# testBoard.net
KiCad netlist of a schematic drawn in EAGLE
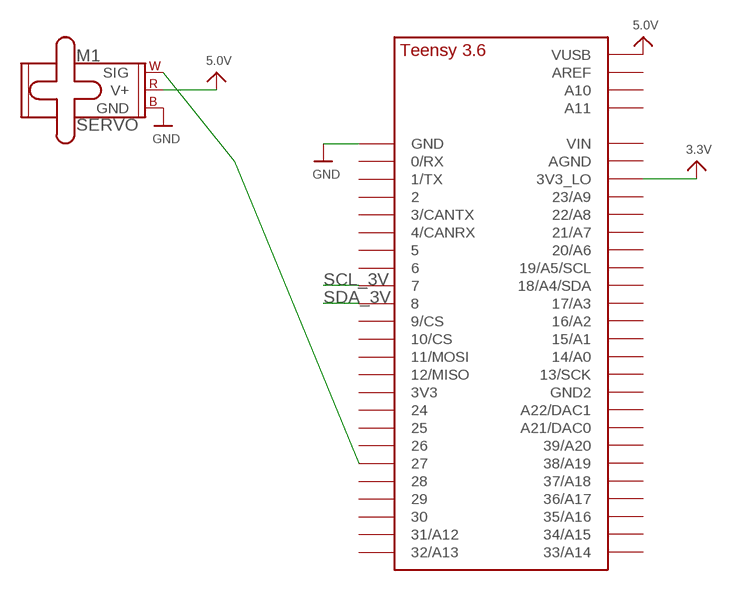
[diagram p0: schematic, sheet 1]
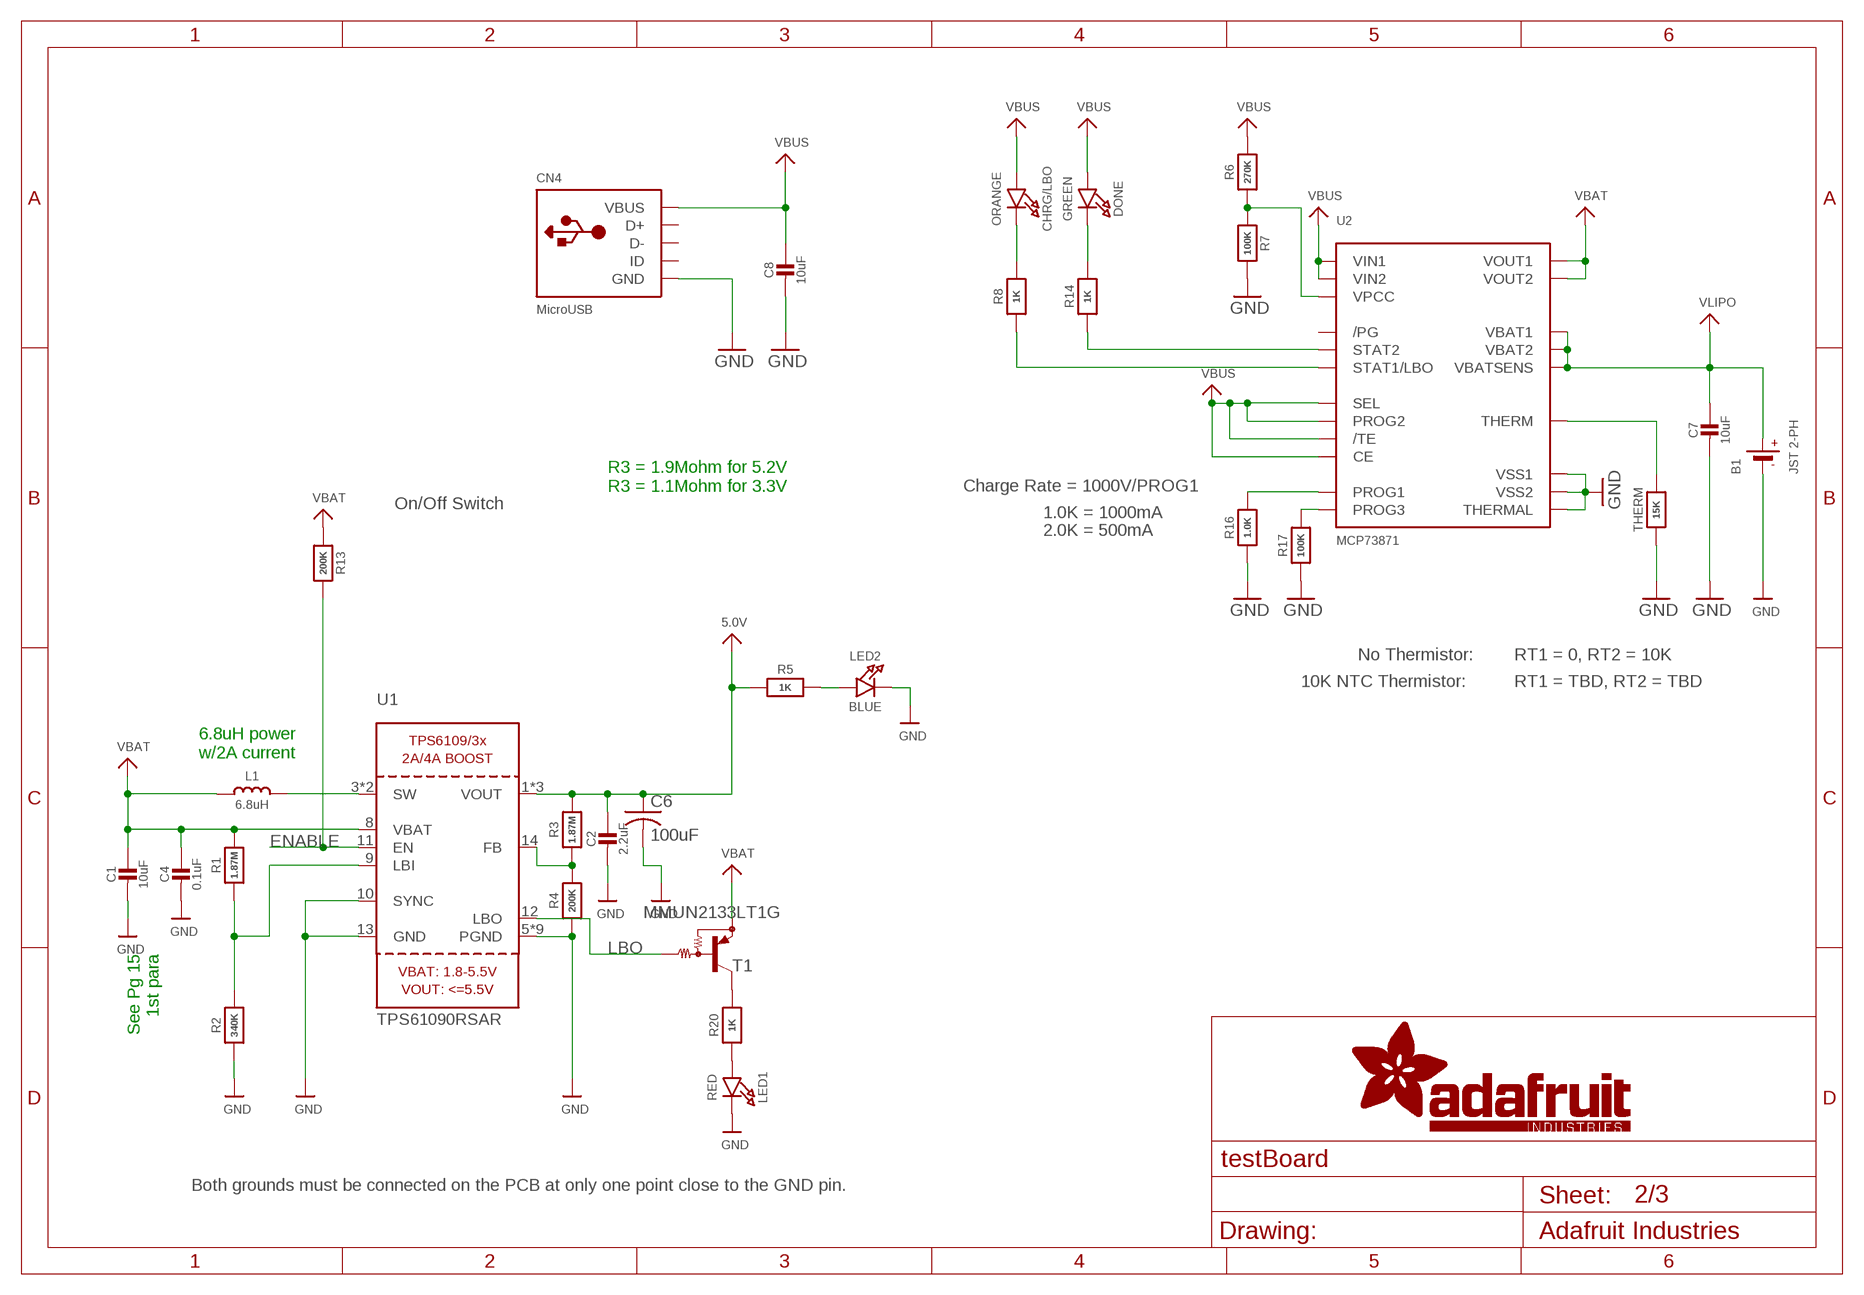
[diagram p1: schematic, sheet 2]
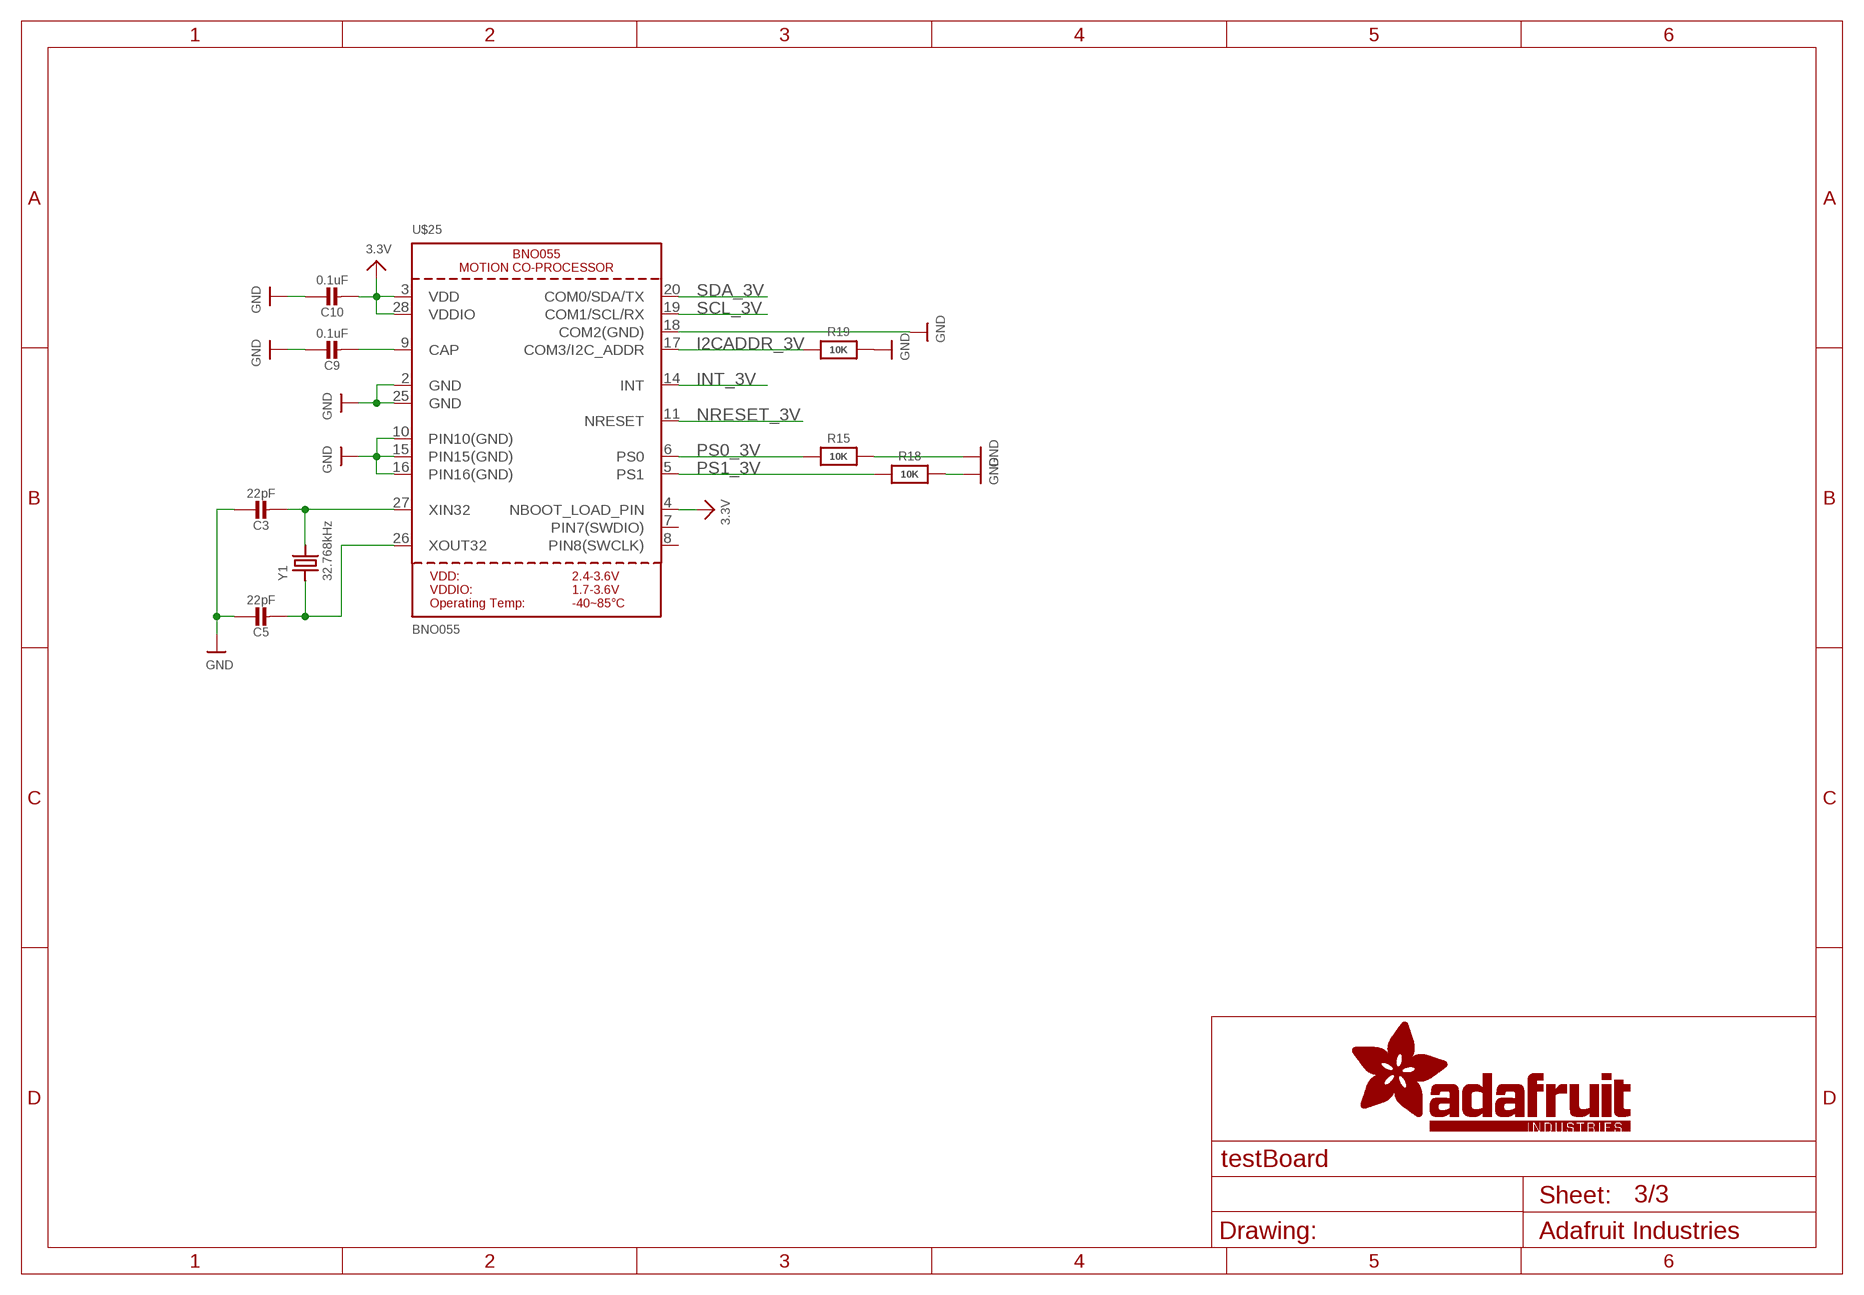
[diagram p2: schematic, sheet 3]

(export (version "E")
  (design (tool "Eeschema 10.0.6"))
  (components
    (comp (ref "B1")
      (value "JST 2-PH")
      (footprint "eagle-import:JSTPH2")
      (libsource (lib "eagle-import") (part "BATTERY"))
    )
    (comp (ref "C1")
      (value "10uF")
      (footprint "eagle-import:0805-NO")
      (libsource (lib "eagle-import") (part "CAP_CERAMIC0805-NOOUTLINE"))
    )
    (comp (ref "C2")
      (value "2.2uF")
      (footprint "eagle-import:0805-NO")
      (libsource (lib "eagle-import") (part "CAP_CERAMIC0805-NOOUTLINE"))
    )
    (comp (ref "C4")
      (value "0.1uF")
      (footprint "eagle-import:0805_10MGAP")
      (libsource (lib "eagle-import") (part "CAP_CERAMIC0805_10MGAP"))
    )
    (comp (ref "C6")
      (value "100uF")
      (footprint "eagle-import:C1210")
      (libsource (lib "eagle-import") (part "C-USC1210"))
    )
    (comp (ref "C7")
      (value "10uF")
      (footprint "eagle-import:0805-NO")
      (libsource (lib "eagle-import") (part "CAP_CERAMIC0805-NOOUTLINE"))
    )
    (comp (ref "C8")
      (value "10uF")
      (footprint "eagle-import:0805-NO")
      (libsource (lib "eagle-import") (part "CAP_CERAMIC0805-NOOUTLINE"))
    )
    (comp (ref "CHRG/LBO")
      (value "ORANGE")
      (footprint "eagle-import:CHIPLED_0805_NOOUTLINE")
      (libsource (lib "eagle-import") (part "LED0805_NOOUTLINE"))
    )
    (comp (ref "CN4")
      (value "MicroUSB")
      (footprint "eagle-import:4UCONN_20329")
      (libsource (lib "eagle-import") (part "USBMICRO_20329"))
    )
    (comp (ref "DONE")
      (value "GREEN")
      (footprint "eagle-import:CHIPLED_0805_NOOUTLINE")
      (libsource (lib "eagle-import") (part "LED0805_NOOUTLINE"))
    )
    (comp (ref "L1")
      (value "6.8uH")
      (footprint "eagle-import:INDUCTOR_5X5MM_TDK_VLC5045")
      (libsource (lib "eagle-import") (part "INDUCTORTDK_VLC5045"))
    )
    (comp (ref "LED1")
      (value "RED")
      (footprint "eagle-import:CHIPLED_0805_NOOUTLINE")
      (libsource (lib "eagle-import") (part "LED0805_NOOUTLINE"))
    )
    (comp (ref "LED2")
      (value "BLUE")
      (footprint "eagle-import:CHIPLED_0805_NOOUTLINE")
      (libsource (lib "eagle-import") (part "LED0805_NOOUTLINE"))
    )
    (comp (ref "R1")
      (value "1.87M")
      (footprint "eagle-import:_0805MP")
      (libsource (lib "eagle-import") (part "RESISTOR_0805MP"))
    )
    (comp (ref "R2")
      (value "340K")
      (footprint "eagle-import:_0805MP")
      (libsource (lib "eagle-import") (part "RESISTOR_0805MP"))
    )
    (comp (ref "R3")
      (value "1.87M")
      (footprint "eagle-import:0805-NO")
      (libsource (lib "eagle-import") (part "RESISTOR0805_NOOUTLINE"))
    )
    (comp (ref "R4")
      (value "200K")
      (footprint "eagle-import:0805-NO")
      (libsource (lib "eagle-import") (part "RESISTOR0805_NOOUTLINE"))
    )
    (comp (ref "R5")
      (value "1K")
      (footprint "eagle-import:0805-NO")
      (libsource (lib "eagle-import") (part "RESISTOR0805_NOOUTLINE"))
    )
    (comp (ref "R6")
      (value "270K")
      (footprint "eagle-import:0805-NO")
      (libsource (lib "eagle-import") (part "RESISTOR0805_NOOUTLINE"))
    )
    (comp (ref "R7")
      (value "100K")
      (footprint "eagle-import:0805-NO")
      (libsource (lib "eagle-import") (part "RESISTOR0805_NOOUTLINE"))
    )
    (comp (ref "R8")
      (value "1K")
      (footprint "eagle-import:0805-NO")
      (libsource (lib "eagle-import") (part "RESISTOR0805_NOOUTLINE"))
    )
    (comp (ref "R13")
      (value "200K")
      (footprint "eagle-import:0805-NO")
      (libsource (lib "eagle-import") (part "RESISTOR0805_NOOUTLINE"))
    )
    (comp (ref "R14")
      (value "1K")
      (footprint "eagle-import:0805-NO")
      (libsource (lib "eagle-import") (part "RESISTOR0805_NOOUTLINE"))
    )
    (comp (ref "R16")
      (value "1.0K")
      (footprint "eagle-import:0805-NO")
      (libsource (lib "eagle-import") (part "RESISTOR0805_NOOUTLINE"))
    )
    (comp (ref "R17")
      (value "100K")
      (footprint "eagle-import:0805-NO")
      (libsource (lib "eagle-import") (part "RESISTOR0805_NOOUTLINE"))
    )
    (comp (ref "R20")
      (value "1K")
      (footprint "eagle-import:0805-NO")
      (libsource (lib "eagle-import") (part "RESISTOR0805_NOOUTLINE"))
    )
    (comp (ref "T1")
      (value "MMUN2133LT1G")
      (footprint "eagle-import:SC59-BEC")
      (libsource (lib "eagle-import") (part "-PNP_DRIVER-SC59-BECMUN2114T1"))
    )
    (comp (ref "THERM")
      (value "15K")
      (footprint "eagle-import:0805-NO")
      (libsource (lib "eagle-import") (part "RESISTOR0805_NOOUTLINE"))
    )
    (comp (ref "U1")
      (value "TPS61090RSAR")
      (footprint "eagle-import:PVQFN-16")
      (libsource (lib "eagle-import") (part "VREG_TPS6103X"))
    )
    (comp (ref "U2")
      (value "MCP73871")
      (footprint "eagle-import:QFN20_4MM")
      (libsource (lib "eagle-import") (part "MCP73871"))
    )
    (comp (ref "M1")
      (value "SERVO")
      (footprint "eagle-import:1X03")
      (libsource (lib "eagle-import") (part "SERVO"))
    )
    (comp (ref "U$69")
      (value "TEENSY_3.5/3.6_BASIC")
      (footprint "eagle-import:TEENSY_3.5_3.6_BASIC")
      (libsource (lib "eagle-import") (part "TEENSY_3.5/3.6_BASIC"))
    )
    (comp (ref "C3")
      (value "22pF")
      (footprint "eagle-import:0805-NO")
      (libsource (lib "eagle-import") (part "CAP_CERAMIC0805-NOOUTLINE"))
    )
    (comp (ref "C5")
      (value "22pF")
      (footprint "eagle-import:0805-NO")
      (libsource (lib "eagle-import") (part "CAP_CERAMIC0805-NOOUTLINE"))
    )
    (comp (ref "C9")
      (value "0.1uF")
      (footprint "eagle-import:0805-NO")
      (libsource (lib "eagle-import") (part "CAP_CERAMIC0805-NOOUTLINE"))
    )
    (comp (ref "C10")
      (value "0.1uF")
      (footprint "eagle-import:0805_10MGAP")
      (libsource (lib "eagle-import") (part "CAP_CERAMIC0805_10MGAP"))
    )
    (comp (ref "R15")
      (value "10K")
      (footprint "eagle-import:0805-NO")
      (libsource (lib "eagle-import") (part "RESISTOR0805_NOOUTLINE"))
    )
    (comp (ref "R18")
      (value "10K")
      (footprint "eagle-import:0805-NO")
      (libsource (lib "eagle-import") (part "RESISTOR0805_NOOUTLINE"))
    )
    (comp (ref "R19")
      (value "10K")
      (footprint "eagle-import:0805-NO")
      (libsource (lib "eagle-import") (part "RESISTOR0805_NOOUTLINE"))
    )
    (comp (ref "U$25")
      (value "BNO055")
      (footprint "eagle-import:BNO055")
      (libsource (lib "eagle-import") (part "BNO055"))
    )
    (comp (ref "Y1")
      (value "32.768kHz")
      (footprint "eagle-import:CRYSTAL_8X3.8")
      (libsource (lib "eagle-import") (part "CRYSTAL8.0X3.8"))
    )
  )
  (nets
    (net (code "1") (name "3.3V") (class "Default")
      (node (ref "C10") (pin "2") (pinfunction "2_2") (pintype "passive"))
      (node (ref "U$25") (pin "28") (pinfunction "VDDIO_28") (pintype "power_in"))
      (node (ref "U$25") (pin "3") (pinfunction "VDD_3") (pintype "power_in"))
      (node (ref "U$25") (pin "4") (pinfunction "NBOOT_LOAD_PIN_4") (pintype "bidirectional"))
      (node (ref "U$69") (pin "3V3_LO") (pinfunction "3V3_LO_3V3_LO") (pintype "bidirectional"))
    )
    (net (code "2") (name "5.0V") (class "Default")
      (node (ref "C2") (pin "1") (pinfunction "1_1") (pintype "passive"))
      (node (ref "C6") (pin "1") (pinfunction "1_1") (pintype "passive"))
      (node (ref "M1") (pin "2") (pinfunction "V+_2") (pintype "bidirectional"))
      (node (ref "R3") (pin "2") (pinfunction "2_2") (pintype "passive"))
      (node (ref "R5") (pin "1") (pinfunction "1_1") (pintype "passive"))
      (node (ref "U$69") (pin "VUSB") (pinfunction "VUSB_VUSB") (pintype "bidirectional"))
      (node (ref "U1") (pin "1") (pinfunction "VOUT_1") (pintype "power_in"))
      (node (ref "U1") (pin "15") (pinfunction "VOUT_15") (pintype "power_in"))
      (node (ref "U1") (pin "16") (pinfunction "VOUT_16") (pintype "power_in"))
    )
    (net (code "3") (name "ENABLE") (class "Default")
      (node (ref "R13") (pin "2") (pinfunction "2_2") (pintype "passive"))
      (node (ref "U1") (pin "11") (pinfunction "EN_11") (pintype "input"))
    )
    (net (code "4") (name "GND") (class "Default")
      (node (ref "B1") (pin "1") (pinfunction "-_1") (pintype "passive"))
      (node (ref "C1") (pin "2") (pinfunction "2_2") (pintype "passive"))
      (node (ref "C10") (pin "1") (pinfunction "1_1") (pintype "passive"))
      (node (ref "C2") (pin "2") (pinfunction "2_2") (pintype "passive"))
      (node (ref "C3") (pin "1") (pinfunction "1_1") (pintype "passive"))
      (node (ref "C4") (pin "2") (pinfunction "2_2") (pintype "passive"))
      (node (ref "C5") (pin "1") (pinfunction "1_1") (pintype "passive"))
      (node (ref "C6") (pin "2") (pinfunction "2_2") (pintype "passive"))
      (node (ref "C7") (pin "2") (pinfunction "2_2") (pintype "passive"))
      (node (ref "C8") (pin "2") (pinfunction "2_2") (pintype "passive"))
      (node (ref "C9") (pin "1") (pinfunction "1_1") (pintype "passive"))
      (node (ref "CN4") (pin "BASE@1") (pinfunction "GND_BASE@1") (pintype "power_in"))
      (node (ref "CN4") (pin "BASE@2") (pinfunction "GND_BASE@2") (pintype "power_in"))
      (node (ref "CN4") (pin "GND") (pinfunction "GND_GND") (pintype "power_in"))
      (node (ref "CN4") (pin "SPRT@1") (pinfunction "GND_SPRT@1") (pintype "power_in"))
      (node (ref "CN4") (pin "SPRT@2") (pinfunction "GND_SPRT@2") (pintype "power_in"))
      (node (ref "CN4") (pin "SPRT@3") (pinfunction "GND_SPRT@3") (pintype "power_in"))
      (node (ref "CN4") (pin "SPRT@4") (pinfunction "GND_SPRT@4") (pintype "power_in"))
      (node (ref "LED1") (pin "C") (pinfunction "C_C") (pintype "passive"))
      (node (ref "LED2") (pin "C") (pinfunction "C_C") (pintype "passive"))
      (node (ref "M1") (pin "3") (pinfunction "GND_3") (pintype "bidirectional"))
      (node (ref "R15") (pin "2") (pinfunction "2_2") (pintype "passive"))
      (node (ref "R16") (pin "1") (pinfunction "1_1") (pintype "passive"))
      (node (ref "R17") (pin "1") (pinfunction "1_1") (pintype "passive"))
      (node (ref "R18") (pin "2") (pinfunction "2_2") (pintype "passive"))
      (node (ref "R19") (pin "2") (pinfunction "2_2") (pintype "passive"))
      (node (ref "R2") (pin "1") (pinfunction "1_1") (pintype "passive"))
      (node (ref "R4") (pin "1") (pinfunction "1_1") (pintype "passive"))
      (node (ref "R7") (pin "2") (pinfunction "2_2") (pintype "passive"))
      (node (ref "THERM") (pin "1") (pinfunction "1_1") (pintype "passive"))
      (node (ref "U$25") (pin "10") (pinfunction "PIN10(GND)_10") (pintype "bidirectional"))
      (node (ref "U$25") (pin "15") (pinfunction "PIN15(GND)_15") (pintype "bidirectional"))
      (node (ref "U$25") (pin "16") (pinfunction "PIN16(GND)_16") (pintype "bidirectional"))
      (node (ref "U$25") (pin "18") (pinfunction "COM2(GND)_18") (pintype "bidirectional"))
      (node (ref "U$25") (pin "2") (pinfunction "GND_2") (pintype "power_in"))
      (node (ref "U$25") (pin "25") (pinfunction "GND_25") (pintype "power_in"))
      (node (ref "U$69") (pin "GND") (pinfunction "GND_GND") (pintype "bidirectional"))
      (node (ref "U1") (pin "10") (pinfunction "SYNC_10") (pintype "input"))
      (node (ref "U1") (pin "13") (pinfunction "GND_13") (pintype "power_in"))
      (node (ref "U1") (pin "5") (pinfunction "PGND_5") (pintype "power_in"))
      (node (ref "U1") (pin "6") (pinfunction "PGND_6") (pintype "power_in"))
      (node (ref "U1") (pin "7") (pinfunction "PGND_7") (pintype "power_in"))
      (node (ref "U1") (pin "P$18") (pinfunction "PGND_P$18") (pintype "power_in"))
      (node (ref "U1") (pin "P$19") (pinfunction "PGND_P$19") (pintype "power_in"))
      (node (ref "U1") (pin "P$20") (pinfunction "PGND_P$20") (pintype "power_in"))
      (node (ref "U1") (pin "P$21") (pinfunction "PGND_P$21") (pintype "power_in"))
      (node (ref "U1") (pin "P$22") (pinfunction "PGND_P$22") (pintype "power_in"))
      (node (ref "U1") (pin "THERMAL") (pinfunction "PGND_THERMAL") (pintype "power_in"))
      (node (ref "U2") (pin "P$10") (pinfunction "VSS1_P$10") (pintype "bidirectional"))
      (node (ref "U2") (pin "P$11") (pinfunction "VSS2_P$11") (pintype "bidirectional"))
      (node (ref "U2") (pin "P$21") (pinfunction "THERMAL_P$21") (pintype "bidirectional"))
    )
    (net (code "5") (name "I2CADDR_3V") (class "Default")
      (node (ref "R19") (pin "1") (pinfunction "1_1") (pintype "passive"))
      (node (ref "U$25") (pin "17") (pinfunction "COM3/I2C_ADDR_17") (pintype "bidirectional"))
    )
    (net (code "6") (name "INT_3V") (class "Default")
      (node (ref "U$25") (pin "14") (pinfunction "INT_14") (pintype "output"))
    )
    (net (code "7") (name "LBO") (class "Default")
      (node (ref "T1") (pin "B") (pinfunction "B_B") (pintype "passive"))
      (node (ref "U1") (pin "12") (pinfunction "LBO_12") (pintype "output"))
    )
    (net (code "8") (name "NRESET_3V") (class "Default")
      (node (ref "U$25") (pin "11") (pinfunction "NRESET_11") (pintype "bidirectional"))
    )
    (net (code "9") (name "Net-(CHRG/LBO-PadC)") (class "Default")
      (node (ref "CHRG/LBO") (pin "C") (pinfunction "C_C") (pintype "passive"))
      (node (ref "R8") (pin "2") (pinfunction "2_2") (pintype "passive"))
    )
    (net (code "10") (name "Net-(DONE-PadC)") (class "Default")
      (node (ref "DONE") (pin "C") (pinfunction "C_C") (pintype "passive"))
      (node (ref "R14") (pin "2") (pinfunction "2_2") (pintype "passive"))
    )
    (net (code "11") (name "Net-(L1-2)") (class "Default")
      (node (ref "L1") (pin "P$2") (pinfunction "2_P$2") (pintype "passive"))
      (node (ref "U1") (pin "3") (pinfunction "SW_3") (pintype "input"))
      (node (ref "U1") (pin "4") (pinfunction "SW_4") (pintype "input"))
    )
    (net (code "12") (name "Net-(LED1-PadA)") (class "Default")
      (node (ref "LED1") (pin "A") (pinfunction "A_A") (pintype "passive"))
      (node (ref "R20") (pin "1") (pinfunction "1_1") (pintype "passive"))
    )
    (net (code "13") (name "Net-(LED2-PadA)") (class "Default")
      (node (ref "LED2") (pin "A") (pinfunction "A_A") (pintype "passive"))
      (node (ref "R5") (pin "2") (pinfunction "2_2") (pintype "passive"))
    )
    (net (code "14") (name "Net-(M1-SIG)") (class "Default")
      (node (ref "M1") (pin "1") (pinfunction "SIG_1") (pintype "bidirectional"))
      (node (ref "U$69") (pin "27") (pinfunction "27_27") (pintype "bidirectional"))
    )
    (net (code "15") (name "Net-(R20-Pad2)") (class "Default")
      (node (ref "R20") (pin "2") (pinfunction "2_2") (pintype "passive"))
      (node (ref "T1") (pin "C") (pinfunction "C_C") (pintype "passive"))
    )
    (net (code "16") (name "Net-(U$25-CAP)") (class "Default")
      (node (ref "C9") (pin "2") (pinfunction "2_2") (pintype "passive"))
      (node (ref "U$25") (pin "9") (pinfunction "CAP_9") (pintype "passive"))
    )
    (net (code "17") (name "Net-(U$25-XIN32)") (class "Default")
      (node (ref "C3") (pin "2") (pinfunction "2_2") (pintype "passive"))
      (node (ref "U$25") (pin "27") (pinfunction "XIN32_27") (pintype "input"))
      (node (ref "Y1") (pin "P$4") (pinfunction "2_P$4") (pintype "passive"))
    )
    (net (code "18") (name "Net-(U$25-XOUT32)") (class "Default")
      (node (ref "C5") (pin "2") (pinfunction "2_2") (pintype "passive"))
      (node (ref "U$25") (pin "26") (pinfunction "XOUT32_26") (pintype "output"))
      (node (ref "Y1") (pin "P$1") (pinfunction "1_P$1") (pintype "passive"))
    )
    (net (code "19") (name "Net-(U1-FB)") (class "Default")
      (node (ref "R3") (pin "1") (pinfunction "1_1") (pintype "passive"))
      (node (ref "R4") (pin "2") (pinfunction "2_2") (pintype "passive"))
      (node (ref "U1") (pin "14") (pinfunction "FB_14") (pintype "input"))
    )
    (net (code "20") (name "Net-(U1-LBI)") (class "Default")
      (node (ref "R1") (pin "1") (pinfunction "1_1") (pintype "passive"))
      (node (ref "R2") (pin "2") (pinfunction "2_2") (pintype "passive"))
      (node (ref "U1") (pin "9") (pinfunction "LBI_9") (pintype "input"))
    )
    (net (code "21") (name "Net-(U2-PROG1)") (class "Default")
      (node (ref "R16") (pin "2") (pinfunction "2_2") (pintype "passive"))
      (node (ref "U2") (pin "P$13") (pinfunction "PROG1_P$13") (pintype "bidirectional"))
    )
    (net (code "22") (name "Net-(U2-PROG3)") (class "Default")
      (node (ref "R17") (pin "2") (pinfunction "2_2") (pintype "passive"))
      (node (ref "U2") (pin "P$12") (pinfunction "PROG3_P$12") (pintype "bidirectional"))
    )
    (net (code "23") (name "Net-(U2-STAT1{slash}LBO)") (class "Default")
      (node (ref "R8") (pin "1") (pinfunction "1_1") (pintype "passive"))
      (node (ref "U2") (pin "P$8") (pinfunction "STAT1/LBO_P$8") (pintype "bidirectional"))
    )
    (net (code "24") (name "Net-(U2-STAT2)") (class "Default")
      (node (ref "R14") (pin "1") (pinfunction "1_1") (pintype "passive"))
      (node (ref "U2") (pin "P$7") (pinfunction "STAT2_P$7") (pintype "bidirectional"))
    )
    (net (code "25") (name "Net-(U2-THERM)") (class "Default")
      (node (ref "THERM") (pin "2") (pinfunction "2_2") (pintype "passive"))
      (node (ref "U2") (pin "P$5") (pinfunction "THERM_P$5") (pintype "bidirectional"))
    )
    (net (code "26") (name "Net-(U2-VPCC)") (class "Default")
      (node (ref "R6") (pin "1") (pinfunction "1_1") (pintype "passive"))
      (node (ref "R7") (pin "1") (pinfunction "1_1") (pintype "passive"))
      (node (ref "U2") (pin "P$2") (pinfunction "VPCC_P$2") (pintype "bidirectional"))
    )
    (net (code "27") (name "PS0_3V") (class "Default")
      (node (ref "R15") (pin "1") (pinfunction "1_1") (pintype "passive"))
      (node (ref "U$25") (pin "6") (pinfunction "PS0_6") (pintype "input"))
    )
    (net (code "28") (name "PS1_3V") (class "Default")
      (node (ref "R18") (pin "1") (pinfunction "1_1") (pintype "passive"))
      (node (ref "U$25") (pin "5") (pinfunction "PS1_5") (pintype "input"))
    )
    (net (code "29") (name "SCL_3V") (class "Default")
      (node (ref "U$25") (pin "19") (pinfunction "COM1/SCL/RX_19") (pintype "bidirectional"))
      (node (ref "U$69") (pin "7") (pinfunction "7_7") (pintype "bidirectional"))
    )
    (net (code "30") (name "SDA_3V") (class "Default")
      (node (ref "U$25") (pin "20") (pinfunction "COM0/SDA/TX_20") (pintype "bidirectional"))
      (node (ref "U$69") (pin "8") (pinfunction "8_8") (pintype "bidirectional"))
    )
    (net (code "31") (name "VBAT") (class "Default")
      (node (ref "C1") (pin "1") (pinfunction "1_1") (pintype "passive"))
      (node (ref "C4") (pin "1") (pinfunction "1_1") (pintype "passive"))
      (node (ref "L1") (pin "P$1") (pinfunction "1_P$1") (pintype "passive"))
      (node (ref "R1") (pin "2") (pinfunction "2_2") (pintype "passive"))
      (node (ref "R13") (pin "1") (pinfunction "1_1") (pintype "passive"))
      (node (ref "T1") (pin "E") (pinfunction "E_E") (pintype "passive"))
      (node (ref "U1") (pin "8") (pinfunction "VBAT_8") (pintype "input"))
      (node (ref "U2") (pin "P$1") (pinfunction "VOUT1_P$1") (pintype "bidirectional"))
      (node (ref "U2") (pin "P$20") (pinfunction "VOUT2_P$20") (pintype "bidirectional"))
    )
    (net (code "32") (name "VBUS") (class "Default")
      (node (ref "C8") (pin "1") (pinfunction "1_1") (pintype "passive"))
      (node (ref "CHRG/LBO") (pin "A") (pinfunction "A_A") (pintype "passive"))
      (node (ref "CN4") (pin "VBUS") (pinfunction "VBUS_VBUS") (pintype "power_in"))
      (node (ref "DONE") (pin "A") (pinfunction "A_A") (pintype "passive"))
      (node (ref "R6") (pin "2") (pinfunction "2_2") (pintype "passive"))
      (node (ref "U2") (pin "P$17") (pinfunction "CE_P$17") (pintype "bidirectional"))
      (node (ref "U2") (pin "P$18") (pinfunction "VIN1_P$18") (pintype "bidirectional"))
      (node (ref "U2") (pin "P$19") (pinfunction "VIN2_P$19") (pintype "bidirectional"))
      (node (ref "U2") (pin "P$3") (pinfunction "SEL_P$3") (pintype "bidirectional"))
      (node (ref "U2") (pin "P$4") (pinfunction "PROG2_P$4") (pintype "bidirectional"))
      (node (ref "U2") (pin "P$9") (pinfunction "/TE_P$9") (pintype "bidirectional"))
    )
    (net (code "33") (name "VLIPO") (class "Default")
      (node (ref "B1") (pin "2") (pinfunction "+_2") (pintype "passive"))
      (node (ref "C7") (pin "1") (pinfunction "1_1") (pintype "passive"))
      (node (ref "U2") (pin "P$14") (pinfunction "VBAT1_P$14") (pintype "bidirectional"))
      (node (ref "U2") (pin "P$15") (pinfunction "VBAT2_P$15") (pintype "bidirectional"))
      (node (ref "U2") (pin "P$16") (pinfunction "VBATSENS_P$16") (pintype "bidirectional"))
    )
    (net (code "34") (name "unconnected-(CN4-PadD+)") (class "Default")
      (node (ref "CN4") (pin "D+") (pinfunction "D+_D+") (pintype "bidirectional"))
    )
    (net (code "35") (name "unconnected-(CN4-PadD-)") (class "Default")
      (node (ref "CN4") (pin "D-") (pinfunction "D-_D-") (pintype "bidirectional"))
    )
    (net (code "36") (name "unconnected-(CN4-PadID)") (class "Default")
      (node (ref "CN4") (pin "ID") (pinfunction "ID_ID") (pintype "bidirectional"))
    )
    (net (code "37") (name "unconnected-(U$25-PIN7(SWDIO)-Pad7)") (class "Default")
      (node (ref "U$25") (pin "7") (pinfunction "PIN7(SWDIO)_7") (pintype "bidirectional"))
    )
    (net (code "38") (name "unconnected-(U$25-PIN8(SWCLK)-Pad8)") (class "Default")
      (node (ref "U$25") (pin "8") (pinfunction "PIN8(SWCLK)_8") (pintype "bidirectional"))
    )
    (net (code "39") (name "unconnected-(U$69-A21{slash}DAC0-Pad21{slash}DAC0)") (class "Default")
      (node (ref "U$69") (pin "21/DAC0") (pinfunction "A21/DAC0_21/DAC0") (pintype "bidirectional"))
    )
    (net (code "40") (name "unconnected-(U$69-Pad0{slash}RX)") (class "Default")
      (node (ref "U$69") (pin "0/RX") (pinfunction "0/RX_0/RX") (pintype "bidirectional"))
    )
    (net (code "41") (name "unconnected-(U$69-Pad1{slash}TX)") (class "Default")
      (node (ref "U$69") (pin "1/TX") (pinfunction "1/TX_1/TX") (pintype "bidirectional"))
    )
    (net (code "42") (name "unconnected-(U$69-Pad2)") (class "Default")
      (node (ref "U$69") (pin "2") (pinfunction "2_2") (pintype "bidirectional"))
    )
    (net (code "43") (name "unconnected-(U$69-Pad3V3)") (class "Default")
      (node (ref "U$69") (pin "3V3") (pinfunction "3V3_3V3") (pintype "bidirectional"))
    )
    (net (code "44") (name "unconnected-(U$69-Pad3{slash}CANTX)") (class "Default")
      (node (ref "U$69") (pin "3/CANTX") (pinfunction "3/CANTX_3/CANTX") (pintype "bidirectional"))
    )
    (net (code "45") (name "unconnected-(U$69-Pad4{slash}CANRX)") (class "Default")
      (node (ref "U$69") (pin "4/CANRX") (pinfunction "4/CANRX_4/CANRX") (pintype "bidirectional"))
    )
    (net (code "46") (name "unconnected-(U$69-Pad5)") (class "Default")
      (node (ref "U$69") (pin "5") (pinfunction "5_5") (pintype "bidirectional"))
    )
    (net (code "47") (name "unconnected-(U$69-Pad6)") (class "Default")
      (node (ref "U$69") (pin "6") (pinfunction "6_6") (pintype "bidirectional"))
    )
    (net (code "48") (name "unconnected-(U$69-Pad9{slash}CS)") (class "Default")
      (node (ref "U$69") (pin "9/CS") (pinfunction "9/CS_9/CS") (pintype "bidirectional"))
    )
    (net (code "49") (name "unconnected-(U$69-Pad10{slash}CS)") (class "Default")
      (node (ref "U$69") (pin "10/CS") (pinfunction "10/CS_10/CS") (pintype "bidirectional"))
    )
    (net (code "50") (name "unconnected-(U$69-Pad11{slash}MOSI)") (class "Default")
      (node (ref "U$69") (pin "11/MOSI") (pinfunction "11/MOSI_11/MOSI") (pintype "bidirectional"))
    )
    (net (code "51") (name "unconnected-(U$69-Pad12{slash}MISO)") (class "Default")
      (node (ref "U$69") (pin "12/MISO") (pinfunction "12/MISO_12/MISO") (pintype "bidirectional"))
    )
    (net (code "52") (name "unconnected-(U$69-Pad13{slash}SCK)") (class "Default")
      (node (ref "U$69") (pin "13/SCK") (pinfunction "13/SCK_13/SCK") (pintype "bidirectional"))
    )
    (net (code "53") (name "unconnected-(U$69-Pad14{slash}A0)") (class "Default")
      (node (ref "U$69") (pin "14/A0") (pinfunction "14/A0_14/A0") (pintype "bidirectional"))
    )
    (net (code "54") (name "unconnected-(U$69-Pad15{slash}A1)") (class "Default")
      (node (ref "U$69") (pin "15/A1") (pinfunction "15/A1_15/A1") (pintype "bidirectional"))
    )
    (net (code "55") (name "unconnected-(U$69-Pad16{slash}A2)") (class "Default")
      (node (ref "U$69") (pin "16/A2") (pinfunction "16/A2_16/A2") (pintype "bidirectional"))
    )
    (net (code "56") (name "unconnected-(U$69-Pad17{slash}A3)") (class "Default")
      (node (ref "U$69") (pin "17/A3") (pinfunction "17/A3_17/A3") (pintype "bidirectional"))
    )
    (net (code "57") (name "unconnected-(U$69-Pad18{slash}A4{slash}SDA)") (class "Default")
      (node (ref "U$69") (pin "18/A4/SDA") (pinfunction "18/A4/SDA_18/A4/SDA") (pintype "bidirectional"))
    )
    (net (code "58") (name "unconnected-(U$69-Pad19{slash}A5{slash}SCL)") (class "Default")
      (node (ref "U$69") (pin "19/A5/SCL") (pinfunction "19/A5/SCL_19/A5/SCL") (pintype "bidirectional"))
    )
    (net (code "59") (name "unconnected-(U$69-Pad20{slash}A6)") (class "Default")
      (node (ref "U$69") (pin "20/A6") (pinfunction "20/A6_20/A6") (pintype "bidirectional"))
    )
    (net (code "60") (name "unconnected-(U$69-Pad21{slash}A7)") (class "Default")
      (node (ref "U$69") (pin "21/A7") (pinfunction "21/A7_21/A7") (pintype "bidirectional"))
    )
    (net (code "61") (name "unconnected-(U$69-Pad22{slash}A8)") (class "Default")
      (node (ref "U$69") (pin "22/A8") (pinfunction "22/A8_22/A8") (pintype "bidirectional"))
    )
    (net (code "62") (name "unconnected-(U$69-Pad23{slash}A9)") (class "Default")
      (node (ref "U$69") (pin "23/A9") (pinfunction "23/A9_23/A9") (pintype "bidirectional"))
    )
    (net (code "63") (name "unconnected-(U$69-Pad24)") (class "Default")
      (node (ref "U$69") (pin "24") (pinfunction "24_24") (pintype "bidirectional"))
    )
    (net (code "64") (name "unconnected-(U$69-Pad25)") (class "Default")
      (node (ref "U$69") (pin "25") (pinfunction "25_25") (pintype "bidirectional"))
    )
    (net (code "65") (name "unconnected-(U$69-Pad26)") (class "Default")
      (node (ref "U$69") (pin "26") (pinfunction "26_26") (pintype "bidirectional"))
    )
    (net (code "66") (name "unconnected-(U$69-Pad28)") (class "Default")
      (node (ref "U$69") (pin "28") (pinfunction "28_28") (pintype "bidirectional"))
    )
    (net (code "67") (name "unconnected-(U$69-Pad29)") (class "Default")
      (node (ref "U$69") (pin "29") (pinfunction "29_29") (pintype "bidirectional"))
    )
    (net (code "68") (name "unconnected-(U$69-Pad30)") (class "Default")
      (node (ref "U$69") (pin "30") (pinfunction "30_30") (pintype "bidirectional"))
    )
    (net (code "69") (name "unconnected-(U$69-Pad31{slash}A12)") (class "Default")
      (node (ref "U$69") (pin "31/A12") (pinfunction "31/A12_31/A12") (pintype "bidirectional"))
    )
    (net (code "70") (name "unconnected-(U$69-Pad32{slash}A13)") (class "Default")
      (node (ref "U$69") (pin "32/A13") (pinfunction "32/A13_32/A13") (pintype "bidirectional"))
    )
    (net (code "71") (name "unconnected-(U$69-Pad33{slash}A14)") (class "Default")
      (node (ref "U$69") (pin "33/A14") (pinfunction "33/A14_33/A14") (pintype "bidirectional"))
    )
    (net (code "72") (name "unconnected-(U$69-Pad34{slash}A15)") (class "Default")
      (node (ref "U$69") (pin "34/A15") (pinfunction "34/A15_34/A15") (pintype "bidirectional"))
    )
    (net (code "73") (name "unconnected-(U$69-Pad35{slash}A16)") (class "Default")
      (node (ref "U$69") (pin "35/A16") (pinfunction "35/A16_35/A16") (pintype "bidirectional"))
    )
    (net (code "74") (name "unconnected-(U$69-Pad36{slash}A17)") (class "Default")
      (node (ref "U$69") (pin "36/A17") (pinfunction "36/A17_36/A17") (pintype "bidirectional"))
    )
    (net (code "75") (name "unconnected-(U$69-Pad37{slash}A18)") (class "Default")
      (node (ref "U$69") (pin "37/A18") (pinfunction "37/A18_37/A18") (pintype "bidirectional"))
    )
    (net (code "76") (name "unconnected-(U$69-Pad38{slash}A19)") (class "Default")
      (node (ref "U$69") (pin "38/A19") (pinfunction "38/A19_38/A19") (pintype "bidirectional"))
    )
    (net (code "77") (name "unconnected-(U$69-Pad39{slash}A20)") (class "Default")
      (node (ref "U$69") (pin "39/A20") (pinfunction "39/A20_39/A20") (pintype "bidirectional"))
    )
    (net (code "78") (name "unconnected-(U$69-PadA10)") (class "Default")
      (node (ref "U$69") (pin "A10") (pinfunction "A10_A10") (pintype "bidirectional"))
    )
    (net (code "79") (name "unconnected-(U$69-PadA11)") (class "Default")
      (node (ref "U$69") (pin "A11") (pinfunction "A11_A11") (pintype "bidirectional"))
    )
    (net (code "80") (name "unconnected-(U$69-PadA22{slash}DAC1)") (class "Default")
      (node (ref "U$69") (pin "A22/DAC1") (pinfunction "A22/DAC1_A22/DAC1") (pintype "bidirectional"))
    )
    (net (code "81") (name "unconnected-(U$69-PadAGND)") (class "Default")
      (node (ref "U$69") (pin "AGND") (pinfunction "AGND_AGND") (pintype "bidirectional"))
    )
    (net (code "82") (name "unconnected-(U$69-PadAREF)") (class "Default")
      (node (ref "U$69") (pin "AREF") (pinfunction "AREF_AREF") (pintype "bidirectional"))
    )
    (net (code "83") (name "unconnected-(U$69-PadGND2)") (class "Default")
      (node (ref "U$69") (pin "GND2") (pinfunction "GND2_GND2") (pintype "bidirectional"))
    )
    (net (code "84") (name "unconnected-(U$69-PadVIN)") (class "Default")
      (node (ref "U$69") (pin "VIN") (pinfunction "VIN_VIN") (pintype "bidirectional"))
    )
    (net (code "85") (name "unconnected-(U2-{slash}PG-PadP$6)") (class "Default")
      (node (ref "U2") (pin "P$6") (pinfunction "/PG_P$6") (pintype "bidirectional"))
    )
  )
)
